# trace_5.net
KiCad netlist of a schematic drawn in Altium Designer
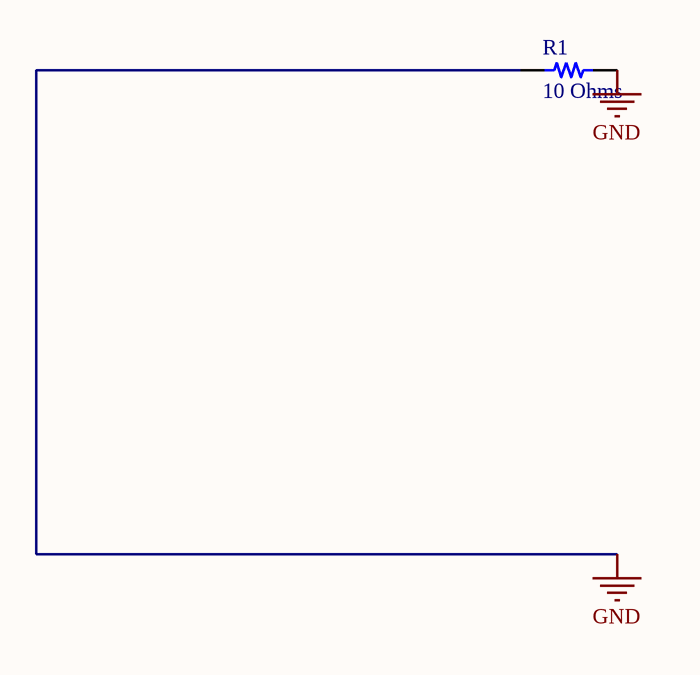
[diagram p0: trace_5.SchDoc]

(export (version "E")
  (design (tool "Eeschema 10.0.6"))
  (components
    (comp (ref "R1")
      (value "10 Ohms")
      (footprint "RES 0201_0603")
      (description "RES SMD 10 OHM 1% 1/20W 0201")
      (fields
        (field (name "PART NUMBER") "CRG0201F10R")
        (field (name "MANUFACTURER") "TE Connectivity Passive Product")
      )
      (libsource (lib "Celestial Altium Library - altium_library") (part "Resistor"))
    )
  )
  (nets
    (net (code "1") (name "GND") (class "Default")
      (node (ref "R1") (pin "1") (pinfunction "1_1") (pintype "passive"))
      (node (ref "R1") (pin "2") (pinfunction "2_2") (pintype "passive"))
    )
  )
)
